# demo.net
KiCad netlist of a schematic drawn in EasyEDA Pro
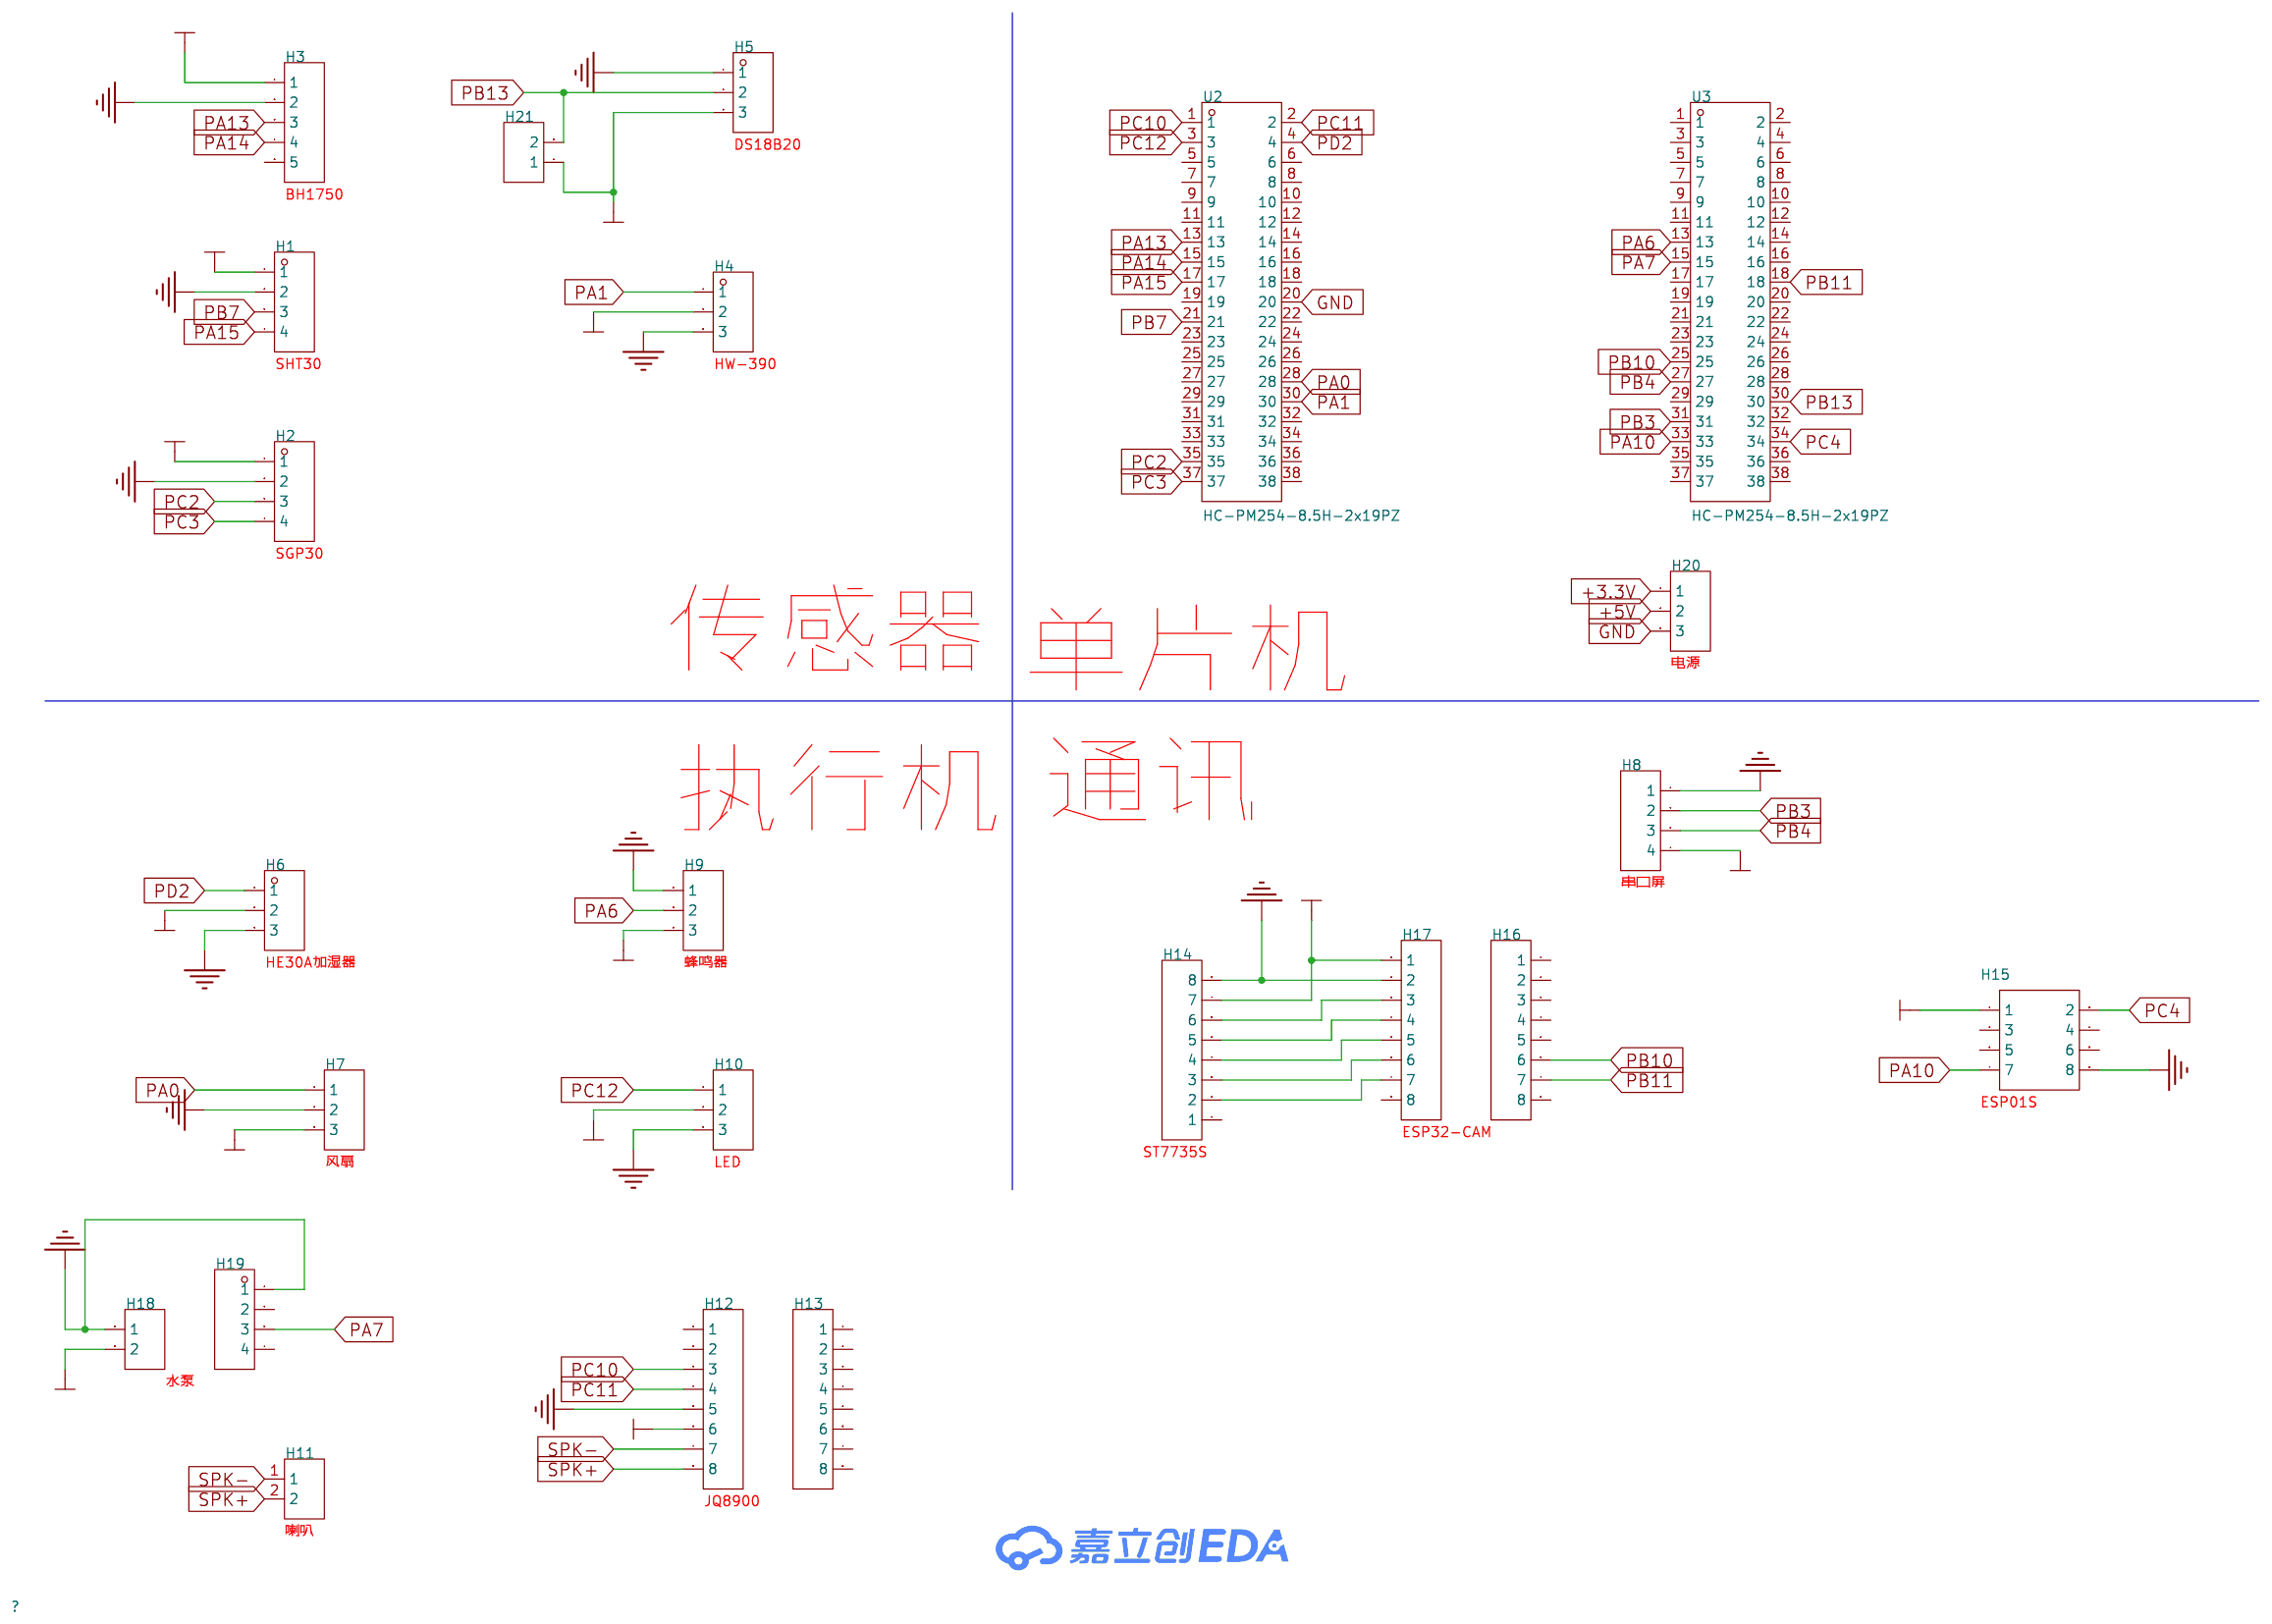
[diagram p0: schematic sheet]

(export (version "E")
  (design (tool "Eeschema 10.0.6"))
  (components
    (comp (ref "H1")
      (value "~")
      (footprint "easyedapro:HDR-TH_4P-P2.54-V-F")
      (libsource (lib "easyedapro") (part "2.54-1*4P母"))
    )
    (comp (ref "H2")
      (value "~")
      (footprint "easyedapro:HDR-TH_4P-P2.54-V-F")
      (libsource (lib "easyedapro") (part "2.54-1*4P母"))
    )
    (comp (ref "H3")
      (value "~")
      (footprint "easyedapro:HDR-TH_5P-P2.54-V-F")
      (libsource (lib "easyedapro") (part "Header-Female-2.54_1x5"))
    )
    (comp (ref "H4")
      (value "~")
      (footprint "easyedapro:HDR-TH_3P-P2.54-V-M")
      (libsource (lib "easyedapro") (part "PZ254V-11-03P_C2937625"))
    )
    (comp (ref "H5")
      (value "~")
      (footprint "easyedapro:HDR-TH_3P-P2.54-V-M")
      (libsource (lib "easyedapro") (part "PZ254V-11-03P_C2937625"))
    )
    (comp (ref "H6")
      (value "~")
      (footprint "easyedapro:HDR-TH_3P-P2.54-V-M")
      (libsource (lib "easyedapro") (part "PZ254V-11-03P_C2937625"))
    )
    (comp (ref "H7")
      (value "~")
      (footprint "easyedapro:HDR-TH_3P-P2.54-V-F")
      (libsource (lib "easyedapro") (part "PM254V-11-03-H85"))
    )
    (comp (ref "H8")
      (value "~")
      (footprint "easyedapro:HDR-TH_4P-P2.54-V-M")
      (libsource (lib "easyedapro") (part "PZ254V-11-04P"))
    )
    (comp (ref "H9")
      (value "~")
      (footprint "easyedapro:HDR-TH_3P-P2.54-V-F")
      (libsource (lib "easyedapro") (part "PM254V-11-03-H85"))
    )
    (comp (ref "H10")
      (value "~")
      (footprint "easyedapro:HDR-TH_3P-P2.54-V-F")
      (libsource (lib "easyedapro") (part "PM254V-11-03-H85"))
    )
    (comp (ref "H11")
      (value "~")
      (footprint "easyedapro:HDR-TH_2P-P2.54-V-M-1")
      (libsource (lib "easyedapro") (part "210S-1*2P L=11.6MMGold-plated black"))
    )
    (comp (ref "H12")
      (value "~")
      (footprint "easyedapro:HDR-TH_8P-P2.54-V-F-1")
      (libsource (lib "easyedapro") (part "Header-Female-2.54_1x8"))
    )
    (comp (ref "H13")
      (value "~")
      (footprint "easyedapro:HDR-TH_8P-P2.54-V-F-1")
      (libsource (lib "easyedapro") (part "Header-Female-2.54_1x8"))
    )
    (comp (ref "H14")
      (value "~")
      (footprint "easyedapro:HDR-TH_8P-P2.54-V-F-1")
      (libsource (lib "easyedapro") (part "Header-Female-2.54_1x8"))
    )
    (comp (ref "H15")
      (value "~")
      (footprint "easyedapro:HDR-TH_8P-P2.54-V-F-R2-C4-S2.54-1")
      (libsource (lib "easyedapro") (part "HDR-F-2.54_2x4"))
    )
    (comp (ref "H16")
      (value "~")
      (footprint "easyedapro:HDR-TH_8P-P2.54-V-F-1")
      (libsource (lib "easyedapro") (part "Header-Female-2.54_1x8"))
    )
    (comp (ref "H17")
      (value "~")
      (footprint "easyedapro:HDR-TH_8P-P2.54-V-F-1")
      (libsource (lib "easyedapro") (part "Header-Female-2.54_1x8"))
    )
    (comp (ref "H18")
      (value "~")
      (footprint "easyedapro:HDR-TH_2P-P2.54-V-F")
      (libsource (lib "easyedapro") (part "Header-Female-2.54_1x2"))
    )
    (comp (ref "H19")
      (value "~")
      (footprint "easyedapro:HDR-TH_4P-P2.54-V-F")
      (libsource (lib "easyedapro") (part "2.54-1*4P母"))
    )
    (comp (ref "H20")
      (value "~")
      (footprint "easyedapro:HDR-TH_3P-P2.54-V-F")
      (libsource (lib "easyedapro") (part "PM254V-11-03-H85"))
    )
    (comp (ref "H21")
      (value "~")
      (footprint "easyedapro:HDR-TH_2P-P2.54-V-F")
      (libsource (lib "easyedapro") (part "Header-Female-2.54_1x2"))
    )
    (comp (ref "U2")
      (value "HC-PM254-8.5H-2x19PZ")
      (footprint "easyedapro:HDR-TH_38P-P2.54-V-F-R2-C19-S2.54")
      (fields (field (name "Manufacturer") "HC(虹成电子)"))
      (libsource (lib "easyedapro") (part "HC-PM254-8.5H-2X19PZ"))
    )
    (comp (ref "U3")
      (value "HC-PM254-8.5H-2x19PZ")
      (footprint "easyedapro:HDR-TH_38P-P2.54-V-F-R2-C19-S2.54")
      (fields (field (name "Manufacturer") "HC(虹成电子)"))
      (libsource (lib "easyedapro") (part "HC-PM254-8.5H-2X19PZ"))
    )
  )
  (nets
    (net (code "1") (name "+3.3V") (class "Default")
      (node (ref "H1") (pin "1") (pinfunction "1_1") (pintype "unspecified"))
      (node (ref "H15") (pin "1") (pinfunction "1_1") (pintype "input"))
      (node (ref "H2") (pin "1") (pinfunction "1_1") (pintype "unspecified"))
      (node (ref "H20") (pin "1") (pinfunction "1_1") (pintype "unspecified"))
      (node (ref "H3") (pin "1") (pinfunction "1_1") (pintype "input"))
      (node (ref "H4") (pin "2") (pinfunction "2_2") (pintype "input"))
      (node (ref "H6") (pin "2") (pinfunction "2_2") (pintype "input"))
      (node (ref "H7") (pin "3") (pinfunction "3_3") (pintype "unspecified"))
      (node (ref "H9") (pin "3") (pinfunction "3_3") (pintype "unspecified"))
    )
    (net (code "2") (name "+5V") (class "Default")
      (node (ref "H10") (pin "2") (pinfunction "2_2") (pintype "unspecified"))
      (node (ref "H12") (pin "6") (pinfunction "6_6") (pintype "input"))
      (node (ref "H14") (pin "7") (pinfunction "7_7") (pintype "input"))
      (node (ref "H17") (pin "1") (pinfunction "1_1") (pintype "input"))
      (node (ref "H18") (pin "2") (pinfunction "2_2") (pintype "input"))
      (node (ref "H20") (pin "2") (pinfunction "2_2") (pintype "unspecified"))
      (node (ref "H21") (pin "1") (pinfunction "1_1") (pintype "input"))
      (node (ref "H5") (pin "3") (pinfunction "3_3") (pintype "input"))
      (node (ref "H8") (pin "4") (pinfunction "4_4") (pintype "unspecified"))
    )
    (net (code "3") (name "GND") (class "Default")
      (node (ref "H1") (pin "2") (pinfunction "2_2") (pintype "unspecified"))
      (node (ref "H10") (pin "3") (pinfunction "3_3") (pintype "unspecified"))
      (node (ref "H12") (pin "5") (pinfunction "5_5") (pintype "input"))
      (node (ref "H14") (pin "8") (pinfunction "8_8") (pintype "input"))
      (node (ref "H15") (pin "8") (pinfunction "8_8") (pintype "input"))
      (node (ref "H17") (pin "2") (pinfunction "2_2") (pintype "input"))
      (node (ref "H18") (pin "1") (pinfunction "1_1") (pintype "input"))
      (node (ref "H19") (pin "1") (pinfunction "1_1") (pintype "unspecified"))
      (node (ref "H2") (pin "2") (pinfunction "2_2") (pintype "unspecified"))
      (node (ref "H20") (pin "3") (pinfunction "3_3") (pintype "unspecified"))
      (node (ref "H3") (pin "2") (pinfunction "2_2") (pintype "input"))
      (node (ref "H4") (pin "3") (pinfunction "3_3") (pintype "input"))
      (node (ref "H5") (pin "1") (pinfunction "1_1") (pintype "input"))
      (node (ref "H6") (pin "3") (pinfunction "3_3") (pintype "input"))
      (node (ref "H7") (pin "2") (pinfunction "2_2") (pintype "unspecified"))
      (node (ref "H8") (pin "1") (pinfunction "1_1") (pintype "unspecified"))
      (node (ref "H9") (pin "1") (pinfunction "1_1") (pintype "unspecified"))
      (node (ref "U2") (pin "20") (pinfunction "20_20") (pintype "unspecified"))
    )
    (net (code "4") (name "Net-(H14-Pad2)") (class "Default")
      (node (ref "H14") (pin "2") (pinfunction "2_2") (pintype "input"))
      (node (ref "H17") (pin "7") (pinfunction "7_7") (pintype "input"))
    )
    (net (code "5") (name "Net-(H14-Pad3)") (class "Default")
      (node (ref "H14") (pin "3") (pinfunction "3_3") (pintype "input"))
      (node (ref "H17") (pin "6") (pinfunction "6_6") (pintype "input"))
    )
    (net (code "6") (name "Net-(H14-Pad4)") (class "Default")
      (node (ref "H14") (pin "4") (pinfunction "4_4") (pintype "input"))
      (node (ref "H17") (pin "5") (pinfunction "5_5") (pintype "input"))
    )
    (net (code "7") (name "Net-(H14-Pad5)") (class "Default")
      (node (ref "H14") (pin "5") (pinfunction "5_5") (pintype "input"))
      (node (ref "H17") (pin "4") (pinfunction "4_4") (pintype "input"))
    )
    (net (code "8") (name "Net-(H14-Pad6)") (class "Default")
      (node (ref "H14") (pin "6") (pinfunction "6_6") (pintype "input"))
      (node (ref "H17") (pin "3") (pinfunction "3_3") (pintype "input"))
    )
    (net (code "9") (name "PA0") (class "Default")
      (node (ref "H7") (pin "1") (pinfunction "1_1") (pintype "unspecified"))
      (node (ref "U2") (pin "28") (pinfunction "28_28") (pintype "unspecified"))
    )
    (net (code "10") (name "PA1") (class "Default")
      (node (ref "H4") (pin "1") (pinfunction "1_1") (pintype "input"))
      (node (ref "U2") (pin "30") (pinfunction "30_30") (pintype "unspecified"))
    )
    (net (code "11") (name "PA6") (class "Default")
      (node (ref "H9") (pin "2") (pinfunction "2_2") (pintype "unspecified"))
      (node (ref "U3") (pin "13") (pinfunction "13_13") (pintype "unspecified"))
    )
    (net (code "12") (name "PA7") (class "Default")
      (node (ref "H19") (pin "3") (pinfunction "3_3") (pintype "unspecified"))
      (node (ref "U3") (pin "15") (pinfunction "15_15") (pintype "unspecified"))
    )
    (net (code "13") (name "PA10") (class "Default")
      (node (ref "H15") (pin "7") (pinfunction "7_7") (pintype "input"))
      (node (ref "U3") (pin "33") (pinfunction "33_33") (pintype "unspecified"))
    )
    (net (code "14") (name "PA13") (class "Default")
      (node (ref "H3") (pin "3") (pinfunction "3_3") (pintype "input"))
      (node (ref "U2") (pin "13") (pinfunction "13_13") (pintype "unspecified"))
    )
    (net (code "15") (name "PA14") (class "Default")
      (node (ref "H3") (pin "4") (pinfunction "4_4") (pintype "input"))
      (node (ref "U2") (pin "15") (pinfunction "15_15") (pintype "unspecified"))
    )
    (net (code "16") (name "PA15") (class "Default")
      (node (ref "H1") (pin "4") (pinfunction "4_4") (pintype "unspecified"))
      (node (ref "U2") (pin "17") (pinfunction "17_17") (pintype "unspecified"))
    )
    (net (code "17") (name "PB3") (class "Default")
      (node (ref "H8") (pin "2") (pinfunction "2_2") (pintype "unspecified"))
      (node (ref "U3") (pin "31") (pinfunction "31_31") (pintype "unspecified"))
    )
    (net (code "18") (name "PB4") (class "Default")
      (node (ref "H8") (pin "3") (pinfunction "3_3") (pintype "unspecified"))
      (node (ref "U3") (pin "27") (pinfunction "27_27") (pintype "unspecified"))
    )
    (net (code "19") (name "PB7") (class "Default")
      (node (ref "H1") (pin "3") (pinfunction "3_3") (pintype "unspecified"))
      (node (ref "U2") (pin "21") (pinfunction "21_21") (pintype "unspecified"))
    )
    (net (code "20") (name "PB10") (class "Default")
      (node (ref "H16") (pin "6") (pinfunction "6_6") (pintype "input"))
      (node (ref "U3") (pin "25") (pinfunction "25_25") (pintype "unspecified"))
    )
    (net (code "21") (name "PB11") (class "Default")
      (node (ref "H16") (pin "7") (pinfunction "7_7") (pintype "input"))
      (node (ref "U3") (pin "18") (pinfunction "18_18") (pintype "unspecified"))
    )
    (net (code "22") (name "PB13") (class "Default")
      (node (ref "H21") (pin "2") (pinfunction "2_2") (pintype "input"))
      (node (ref "H5") (pin "2") (pinfunction "2_2") (pintype "input"))
      (node (ref "U3") (pin "30") (pinfunction "30_30") (pintype "unspecified"))
    )
    (net (code "23") (name "PC2") (class "Default")
      (node (ref "H2") (pin "3") (pinfunction "3_3") (pintype "unspecified"))
      (node (ref "U2") (pin "35") (pinfunction "35_35") (pintype "unspecified"))
    )
    (net (code "24") (name "PC3") (class "Default")
      (node (ref "H2") (pin "4") (pinfunction "4_4") (pintype "unspecified"))
      (node (ref "U2") (pin "37") (pinfunction "37_37") (pintype "unspecified"))
    )
    (net (code "25") (name "PC4") (class "Default")
      (node (ref "H15") (pin "2") (pinfunction "2_2") (pintype "input"))
      (node (ref "U3") (pin "34") (pinfunction "34_34") (pintype "unspecified"))
    )
    (net (code "26") (name "PC10") (class "Default")
      (node (ref "H12") (pin "3") (pinfunction "3_3") (pintype "input"))
      (node (ref "U2") (pin "1") (pinfunction "1_1") (pintype "unspecified"))
    )
    (net (code "27") (name "PC11") (class "Default")
      (node (ref "H12") (pin "4") (pinfunction "4_4") (pintype "input"))
      (node (ref "U2") (pin "2") (pinfunction "2_2") (pintype "unspecified"))
    )
    (net (code "28") (name "PC12") (class "Default")
      (node (ref "H10") (pin "1") (pinfunction "1_1") (pintype "unspecified"))
      (node (ref "U2") (pin "3") (pinfunction "3_3") (pintype "unspecified"))
    )
    (net (code "29") (name "PD2") (class "Default")
      (node (ref "H6") (pin "1") (pinfunction "1_1") (pintype "input"))
      (node (ref "U2") (pin "4") (pinfunction "4_4") (pintype "unspecified"))
    )
    (net (code "30") (name "SPK+") (class "Default")
      (node (ref "H11") (pin "2") (pinfunction "2_2") (pintype "unspecified"))
      (node (ref "H12") (pin "8") (pinfunction "8_8") (pintype "input"))
    )
    (net (code "31") (name "SPK-") (class "Default")
      (node (ref "H11") (pin "1") (pinfunction "1_1") (pintype "unspecified"))
      (node (ref "H12") (pin "7") (pinfunction "7_7") (pintype "input"))
    )
    (net (code "32") (name "unconnected-(H3-Pad5)") (class "Default")
      (node (ref "H3") (pin "5") (pinfunction "5_5") (pintype "input"))
    )
    (net (code "33") (name "unconnected-(H12-Pad1)") (class "Default")
      (node (ref "H12") (pin "1") (pinfunction "1_1") (pintype "input"))
    )
    (net (code "34") (name "unconnected-(H12-Pad2)") (class "Default")
      (node (ref "H12") (pin "2") (pinfunction "2_2") (pintype "input"))
    )
    (net (code "35") (name "unconnected-(H13-Pad1)") (class "Default")
      (node (ref "H13") (pin "1") (pinfunction "1_1") (pintype "input"))
    )
    (net (code "36") (name "unconnected-(H13-Pad2)") (class "Default")
      (node (ref "H13") (pin "2") (pinfunction "2_2") (pintype "input"))
    )
    (net (code "37") (name "unconnected-(H13-Pad3)") (class "Default")
      (node (ref "H13") (pin "3") (pinfunction "3_3") (pintype "input"))
    )
    (net (code "38") (name "unconnected-(H13-Pad4)") (class "Default")
      (node (ref "H13") (pin "4") (pinfunction "4_4") (pintype "input"))
    )
    (net (code "39") (name "unconnected-(H13-Pad5)") (class "Default")
      (node (ref "H13") (pin "5") (pinfunction "5_5") (pintype "input"))
    )
    (net (code "40") (name "unconnected-(H13-Pad6)") (class "Default")
      (node (ref "H13") (pin "6") (pinfunction "6_6") (pintype "input"))
    )
    (net (code "41") (name "unconnected-(H13-Pad7)") (class "Default")
      (node (ref "H13") (pin "7") (pinfunction "7_7") (pintype "input"))
    )
    (net (code "42") (name "unconnected-(H13-Pad8)") (class "Default")
      (node (ref "H13") (pin "8") (pinfunction "8_8") (pintype "input"))
    )
    (net (code "43") (name "unconnected-(H14-Pad1)") (class "Default")
      (node (ref "H14") (pin "1") (pinfunction "1_1") (pintype "input"))
    )
    (net (code "44") (name "unconnected-(H15-Pad3)") (class "Default")
      (node (ref "H15") (pin "3") (pinfunction "3_3") (pintype "input"))
    )
    (net (code "45") (name "unconnected-(H15-Pad4)") (class "Default")
      (node (ref "H15") (pin "4") (pinfunction "4_4") (pintype "input"))
    )
    (net (code "46") (name "unconnected-(H15-Pad5)") (class "Default")
      (node (ref "H15") (pin "5") (pinfunction "5_5") (pintype "input"))
    )
    (net (code "47") (name "unconnected-(H15-Pad6)") (class "Default")
      (node (ref "H15") (pin "6") (pinfunction "6_6") (pintype "input"))
    )
    (net (code "48") (name "unconnected-(H16-Pad1)") (class "Default")
      (node (ref "H16") (pin "1") (pinfunction "1_1") (pintype "input"))
    )
    (net (code "49") (name "unconnected-(H16-Pad2)") (class "Default")
      (node (ref "H16") (pin "2") (pinfunction "2_2") (pintype "input"))
    )
    (net (code "50") (name "unconnected-(H16-Pad3)") (class "Default")
      (node (ref "H16") (pin "3") (pinfunction "3_3") (pintype "input"))
    )
    (net (code "51") (name "unconnected-(H16-Pad4)") (class "Default")
      (node (ref "H16") (pin "4") (pinfunction "4_4") (pintype "input"))
    )
    (net (code "52") (name "unconnected-(H16-Pad5)") (class "Default")
      (node (ref "H16") (pin "5") (pinfunction "5_5") (pintype "input"))
    )
    (net (code "53") (name "unconnected-(H16-Pad8)") (class "Default")
      (node (ref "H16") (pin "8") (pinfunction "8_8") (pintype "input"))
    )
    (net (code "54") (name "unconnected-(H17-Pad8)") (class "Default")
      (node (ref "H17") (pin "8") (pinfunction "8_8") (pintype "input"))
    )
    (net (code "55") (name "unconnected-(H19-Pad2)") (class "Default")
      (node (ref "H19") (pin "2") (pinfunction "2_2") (pintype "unspecified"))
    )
    (net (code "56") (name "unconnected-(H19-Pad4)") (class "Default")
      (node (ref "H19") (pin "4") (pinfunction "4_4") (pintype "unspecified"))
    )
    (net (code "57") (name "unconnected-(U2-Pad5)") (class "Default")
      (node (ref "U2") (pin "5") (pinfunction "5_5") (pintype "unspecified"))
    )
    (net (code "58") (name "unconnected-(U2-Pad6)") (class "Default")
      (node (ref "U2") (pin "6") (pinfunction "6_6") (pintype "unspecified"))
    )
    (net (code "59") (name "unconnected-(U2-Pad7)") (class "Default")
      (node (ref "U2") (pin "7") (pinfunction "7_7") (pintype "unspecified"))
    )
    (net (code "60") (name "unconnected-(U2-Pad8)") (class "Default")
      (node (ref "U2") (pin "8") (pinfunction "8_8") (pintype "unspecified"))
    )
    (net (code "61") (name "unconnected-(U2-Pad9)") (class "Default")
      (node (ref "U2") (pin "9") (pinfunction "9_9") (pintype "unspecified"))
    )
    (net (code "62") (name "unconnected-(U2-Pad10)") (class "Default")
      (node (ref "U2") (pin "10") (pinfunction "10_10") (pintype "unspecified"))
    )
    (net (code "63") (name "unconnected-(U2-Pad11)") (class "Default")
      (node (ref "U2") (pin "11") (pinfunction "11_11") (pintype "unspecified"))
    )
    (net (code "64") (name "unconnected-(U2-Pad12)") (class "Default")
      (node (ref "U2") (pin "12") (pinfunction "12_12") (pintype "unspecified"))
    )
    (net (code "65") (name "unconnected-(U2-Pad14)") (class "Default")
      (node (ref "U2") (pin "14") (pinfunction "14_14") (pintype "unspecified"))
    )
    (net (code "66") (name "unconnected-(U2-Pad16)") (class "Default")
      (node (ref "U2") (pin "16") (pinfunction "16_16") (pintype "unspecified"))
    )
    (net (code "67") (name "unconnected-(U2-Pad18)") (class "Default")
      (node (ref "U2") (pin "18") (pinfunction "18_18") (pintype "unspecified"))
    )
    (net (code "68") (name "unconnected-(U2-Pad19)") (class "Default")
      (node (ref "U2") (pin "19") (pinfunction "19_19") (pintype "unspecified"))
    )
    (net (code "69") (name "unconnected-(U2-Pad22)") (class "Default")
      (node (ref "U2") (pin "22") (pinfunction "22_22") (pintype "unspecified"))
    )
    (net (code "70") (name "unconnected-(U2-Pad23)") (class "Default")
      (node (ref "U2") (pin "23") (pinfunction "23_23") (pintype "unspecified"))
    )
    (net (code "71") (name "unconnected-(U2-Pad24)") (class "Default")
      (node (ref "U2") (pin "24") (pinfunction "24_24") (pintype "unspecified"))
    )
    (net (code "72") (name "unconnected-(U2-Pad25)") (class "Default")
      (node (ref "U2") (pin "25") (pinfunction "25_25") (pintype "unspecified"))
    )
    (net (code "73") (name "unconnected-(U2-Pad26)") (class "Default")
      (node (ref "U2") (pin "26") (pinfunction "26_26") (pintype "unspecified"))
    )
    (net (code "74") (name "unconnected-(U2-Pad27)") (class "Default")
      (node (ref "U2") (pin "27") (pinfunction "27_27") (pintype "unspecified"))
    )
    (net (code "75") (name "unconnected-(U2-Pad29)") (class "Default")
      (node (ref "U2") (pin "29") (pinfunction "29_29") (pintype "unspecified"))
    )
    (net (code "76") (name "unconnected-(U2-Pad31)") (class "Default")
      (node (ref "U2") (pin "31") (pinfunction "31_31") (pintype "unspecified"))
    )
    (net (code "77") (name "unconnected-(U2-Pad32)") (class "Default")
      (node (ref "U2") (pin "32") (pinfunction "32_32") (pintype "unspecified"))
    )
    (net (code "78") (name "unconnected-(U2-Pad33)") (class "Default")
      (node (ref "U2") (pin "33") (pinfunction "33_33") (pintype "unspecified"))
    )
    (net (code "79") (name "unconnected-(U2-Pad34)") (class "Default")
      (node (ref "U2") (pin "34") (pinfunction "34_34") (pintype "unspecified"))
    )
    (net (code "80") (name "unconnected-(U2-Pad36)") (class "Default")
      (node (ref "U2") (pin "36") (pinfunction "36_36") (pintype "unspecified"))
    )
    (net (code "81") (name "unconnected-(U2-Pad38)") (class "Default")
      (node (ref "U2") (pin "38") (pinfunction "38_38") (pintype "unspecified"))
    )
    (net (code "82") (name "unconnected-(U3-Pad1)") (class "Default")
      (node (ref "U3") (pin "1") (pinfunction "1_1") (pintype "unspecified"))
    )
    (net (code "83") (name "unconnected-(U3-Pad2)") (class "Default")
      (node (ref "U3") (pin "2") (pinfunction "2_2") (pintype "unspecified"))
    )
    (net (code "84") (name "unconnected-(U3-Pad3)") (class "Default")
      (node (ref "U3") (pin "3") (pinfunction "3_3") (pintype "unspecified"))
    )
    (net (code "85") (name "unconnected-(U3-Pad4)") (class "Default")
      (node (ref "U3") (pin "4") (pinfunction "4_4") (pintype "unspecified"))
    )
    (net (code "86") (name "unconnected-(U3-Pad5)") (class "Default")
      (node (ref "U3") (pin "5") (pinfunction "5_5") (pintype "unspecified"))
    )
    (net (code "87") (name "unconnected-(U3-Pad6)") (class "Default")
      (node (ref "U3") (pin "6") (pinfunction "6_6") (pintype "unspecified"))
    )
    (net (code "88") (name "unconnected-(U3-Pad7)") (class "Default")
      (node (ref "U3") (pin "7") (pinfunction "7_7") (pintype "unspecified"))
    )
    (net (code "89") (name "unconnected-(U3-Pad8)") (class "Default")
      (node (ref "U3") (pin "8") (pinfunction "8_8") (pintype "unspecified"))
    )
    (net (code "90") (name "unconnected-(U3-Pad9)") (class "Default")
      (node (ref "U3") (pin "9") (pinfunction "9_9") (pintype "unspecified"))
    )
    (net (code "91") (name "unconnected-(U3-Pad10)") (class "Default")
      (node (ref "U3") (pin "10") (pinfunction "10_10") (pintype "unspecified"))
    )
    (net (code "92") (name "unconnected-(U3-Pad11)") (class "Default")
      (node (ref "U3") (pin "11") (pinfunction "11_11") (pintype "unspecified"))
    )
    (net (code "93") (name "unconnected-(U3-Pad12)") (class "Default")
      (node (ref "U3") (pin "12") (pinfunction "12_12") (pintype "unspecified"))
    )
    (net (code "94") (name "unconnected-(U3-Pad14)") (class "Default")
      (node (ref "U3") (pin "14") (pinfunction "14_14") (pintype "unspecified"))
    )
    (net (code "95") (name "unconnected-(U3-Pad16)") (class "Default")
      (node (ref "U3") (pin "16") (pinfunction "16_16") (pintype "unspecified"))
    )
    (net (code "96") (name "unconnected-(U3-Pad17)") (class "Default")
      (node (ref "U3") (pin "17") (pinfunction "17_17") (pintype "unspecified"))
    )
    (net (code "97") (name "unconnected-(U3-Pad19)") (class "Default")
      (node (ref "U3") (pin "19") (pinfunction "19_19") (pintype "unspecified"))
    )
    (net (code "98") (name "unconnected-(U3-Pad20)") (class "Default")
      (node (ref "U3") (pin "20") (pinfunction "20_20") (pintype "unspecified"))
    )
    (net (code "99") (name "unconnected-(U3-Pad21)") (class "Default")
      (node (ref "U3") (pin "21") (pinfunction "21_21") (pintype "unspecified"))
    )
    (net (code "100") (name "unconnected-(U3-Pad22)") (class "Default")
      (node (ref "U3") (pin "22") (pinfunction "22_22") (pintype "unspecified"))
    )
    (net (code "101") (name "unconnected-(U3-Pad23)") (class "Default")
      (node (ref "U3") (pin "23") (pinfunction "23_23") (pintype "unspecified"))
    )
    (net (code "102") (name "unconnected-(U3-Pad24)") (class "Default")
      (node (ref "U3") (pin "24") (pinfunction "24_24") (pintype "unspecified"))
    )
    (net (code "103") (name "unconnected-(U3-Pad26)") (class "Default")
      (node (ref "U3") (pin "26") (pinfunction "26_26") (pintype "unspecified"))
    )
    (net (code "104") (name "unconnected-(U3-Pad28)") (class "Default")
      (node (ref "U3") (pin "28") (pinfunction "28_28") (pintype "unspecified"))
    )
    (net (code "105") (name "unconnected-(U3-Pad29)") (class "Default")
      (node (ref "U3") (pin "29") (pinfunction "29_29") (pintype "unspecified"))
    )
    (net (code "106") (name "unconnected-(U3-Pad32)") (class "Default")
      (node (ref "U3") (pin "32") (pinfunction "32_32") (pintype "unspecified"))
    )
    (net (code "107") (name "unconnected-(U3-Pad35)") (class "Default")
      (node (ref "U3") (pin "35") (pinfunction "35_35") (pintype "unspecified"))
    )
    (net (code "108") (name "unconnected-(U3-Pad36)") (class "Default")
      (node (ref "U3") (pin "36") (pinfunction "36_36") (pintype "unspecified"))
    )
    (net (code "109") (name "unconnected-(U3-Pad37)") (class "Default")
      (node (ref "U3") (pin "37") (pinfunction "37_37") (pintype "unspecified"))
    )
    (net (code "110") (name "unconnected-(U3-Pad38)") (class "Default")
      (node (ref "U3") (pin "38") (pinfunction "38_38") (pintype "unspecified"))
    )
  )
)
